# TPMS.net
KiCad netlist of a schematic drawn in EAGLE
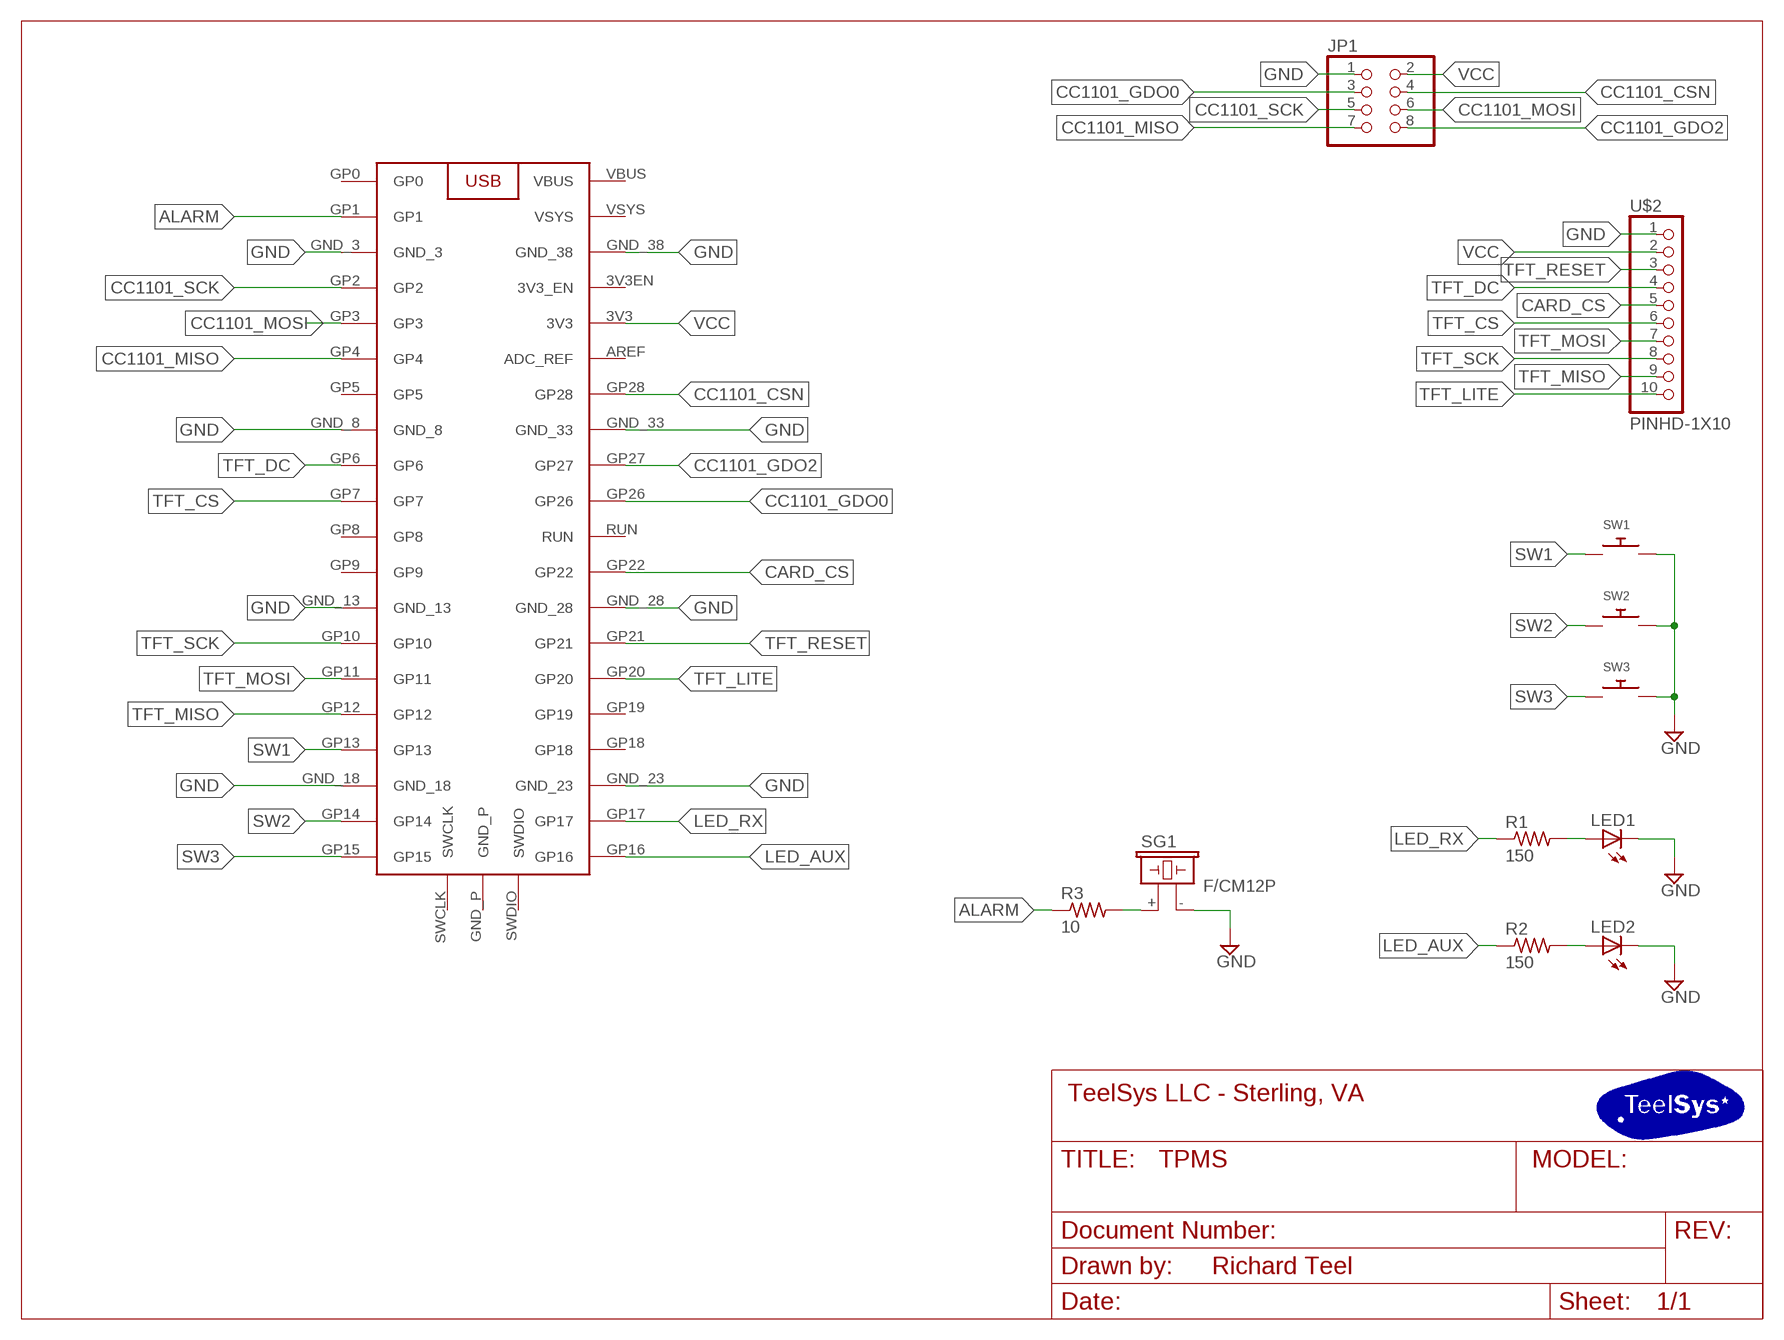
[diagram p0: schematic, sheet 1]

(export (version "E")
  (design (tool "Eeschema 10.0.6"))
  (components
    (comp (ref "JP1")
      (value "PINHD-2X4")
      (footprint "eagle-import:2X04")
      (libsource (lib "eagle-import") (part "PINHD-2X4"))
    )
    (comp (ref "LED1")
      (value "LED3MM")
      (footprint "eagle-import:LED3MM")
      (libsource (lib "eagle-import") (part "LED3MM"))
    )
    (comp (ref "LED2")
      (value "LED3MM")
      (footprint "eagle-import:LED3MM")
      (libsource (lib "eagle-import") (part "LED3MM"))
    )
    (comp (ref "R1")
      (value "150")
      (footprint "eagle-import:M0805")
      (libsource (lib "eagle-import") (part "R-US_M0805"))
    )
    (comp (ref "R2")
      (value "150")
      (footprint "eagle-import:M0805")
      (libsource (lib "eagle-import") (part "R-US_M0805"))
    )
    (comp (ref "R3")
      (value "10")
      (footprint "eagle-import:M0805")
      (libsource (lib "eagle-import") (part "R-US_M0805"))
    )
    (comp (ref "SG1")
      (value "F/CM12P")
      (footprint "eagle-import:F_CM12P")
      (libsource (lib "eagle-import") (part "F/CM12P"))
    )
    (comp (ref "SW1")
      (value "SWITCH_PUSHBUTTONEVQ-PE")
      (footprint "eagle-import:TACT_PANA-EVQ")
      (libsource (lib "eagle-import") (part "SWITCH_PUSHBUTTONEVQ-PE"))
    )
    (comp (ref "SW2")
      (value "SWITCH_PUSHBUTTONEVQ-PE")
      (footprint "eagle-import:TACT_PANA-EVQ")
      (libsource (lib "eagle-import") (part "SWITCH_PUSHBUTTONEVQ-PE"))
    )
    (comp (ref "SW3")
      (value "SWITCH_PUSHBUTTONEVQ-PE")
      (footprint "eagle-import:TACT_PANA-EVQ")
      (libsource (lib "eagle-import") (part "SWITCH_PUSHBUTTONEVQ-PE"))
    )
    (comp (ref "U$1")
      (value "RASPBERRY_PI_PICORASPBERRY_PI_PICO")
      (footprint "eagle-import:RASPBERRY_PI_PICO")
      (libsource (lib "eagle-import") (part "RASPBERRY_PI_PICORASPBERRY_PI_PICO"))
    )
    (comp (ref "U$2")
      (value "PINHD-1X10")
      (footprint "eagle-import:1X10-BIG")
      (libsource (lib "eagle-import") (part "PINHD-1X10"))
    )
  )
  (nets
    (net (code "1") (name "ALARM") (class "Default")
      (node (ref "R3") (pin "1") (pinfunction "1_1") (pintype "passive"))
      (node (ref "U$1") (pin "GP1") (pinfunction "GP1_GP1") (pintype "bidirectional"))
    )
    (net (code "2") (name "CARD_CS") (class "Default")
      (node (ref "U$1") (pin "GP22") (pinfunction "GP22_GP22") (pintype "bidirectional"))
      (node (ref "U$2") (pin "5") (pinfunction "5_5") (pintype "passive"))
    )
    (net (code "3") (name "CC1101_CSN") (class "Default")
      (node (ref "JP1") (pin "4") (pinfunction "4_4") (pintype "passive"))
      (node (ref "U$1") (pin "GP28") (pinfunction "GP28_GP28") (pintype "bidirectional"))
    )
    (net (code "4") (name "CC1101_GDO0") (class "Default")
      (node (ref "JP1") (pin "3") (pinfunction "3_3") (pintype "passive"))
      (node (ref "U$1") (pin "GP26") (pinfunction "GP26_GP26") (pintype "bidirectional"))
    )
    (net (code "5") (name "CC1101_GDO2") (class "Default")
      (node (ref "JP1") (pin "8") (pinfunction "8_8") (pintype "passive"))
      (node (ref "U$1") (pin "GP27") (pinfunction "GP27_GP27") (pintype "bidirectional"))
    )
    (net (code "6") (name "CC1101_MISO") (class "Default")
      (node (ref "JP1") (pin "7") (pinfunction "7_7") (pintype "passive"))
      (node (ref "U$1") (pin "GP4") (pinfunction "GP4_GP4") (pintype "bidirectional"))
    )
    (net (code "7") (name "CC1101_MOSI") (class "Default")
      (node (ref "JP1") (pin "6") (pinfunction "6_6") (pintype "passive"))
      (node (ref "U$1") (pin "GP3") (pinfunction "GP3_GP3") (pintype "bidirectional"))
    )
    (net (code "8") (name "CC1101_SCK") (class "Default")
      (node (ref "JP1") (pin "5") (pinfunction "5_5") (pintype "passive"))
      (node (ref "U$1") (pin "GP2") (pinfunction "GP2_GP2") (pintype "bidirectional"))
    )
    (net (code "9") (name "GND") (class "Default")
      (node (ref "JP1") (pin "1") (pinfunction "1_1") (pintype "passive"))
      (node (ref "LED1") (pin "K") (pinfunction "C_K") (pintype "passive"))
      (node (ref "LED2") (pin "K") (pinfunction "C_K") (pintype "passive"))
      (node (ref "SG1") (pin "-") (pinfunction "2_-") (pintype "passive"))
      (node (ref "SW1") (pin "P$2") (pinfunction "P$2_P$2") (pintype "passive"))
      (node (ref "SW2") (pin "P$2") (pinfunction "P$2_P$2") (pintype "passive"))
      (node (ref "SW3") (pin "P$2") (pinfunction "P$2_P$2") (pintype "passive"))
      (node (ref "U$1") (pin "GND_13") (pinfunction "GND_13_GND_13") (pintype "bidirectional"))
      (node (ref "U$1") (pin "GND_18") (pinfunction "GND_18_GND_18") (pintype "bidirectional"))
      (node (ref "U$1") (pin "GND_23") (pinfunction "GND_23_GND_23") (pintype "bidirectional"))
      (node (ref "U$1") (pin "GND_28") (pinfunction "GND_28_GND_28") (pintype "bidirectional"))
      (node (ref "U$1") (pin "GND_3") (pinfunction "GND_3_GND_3") (pintype "bidirectional"))
      (node (ref "U$1") (pin "GND_33") (pinfunction "GND_33_GND_33") (pintype "bidirectional"))
      (node (ref "U$1") (pin "GND_38") (pinfunction "GND_38_GND_38") (pintype "bidirectional"))
      (node (ref "U$1") (pin "GND_8") (pinfunction "GND_8_GND_8") (pintype "bidirectional"))
      (node (ref "U$2") (pin "1") (pinfunction "1_1") (pintype "passive"))
    )
    (net (code "10") (name "LED_AUX") (class "Default")
      (node (ref "R2") (pin "1") (pinfunction "1_1") (pintype "passive"))
      (node (ref "U$1") (pin "GP16") (pinfunction "GP16_GP16") (pintype "bidirectional"))
    )
    (net (code "11") (name "LED_RX") (class "Default")
      (node (ref "R1") (pin "1") (pinfunction "1_1") (pintype "passive"))
      (node (ref "U$1") (pin "GP17") (pinfunction "GP17_GP17") (pintype "bidirectional"))
    )
    (net (code "12") (name "Net-(LED1-PadA)") (class "Default")
      (node (ref "LED1") (pin "A") (pinfunction "A_A") (pintype "passive"))
      (node (ref "R1") (pin "2") (pinfunction "2_2") (pintype "passive"))
    )
    (net (code "13") (name "Net-(LED2-PadA)") (class "Default")
      (node (ref "LED2") (pin "A") (pinfunction "A_A") (pintype "passive"))
      (node (ref "R2") (pin "2") (pinfunction "2_2") (pintype "passive"))
    )
    (net (code "14") (name "Net-(SG1-1)") (class "Default")
      (node (ref "R3") (pin "2") (pinfunction "2_2") (pintype "passive"))
      (node (ref "SG1") (pin "+") (pinfunction "1_+") (pintype "passive"))
    )
    (net (code "15") (name "SW1") (class "Default")
      (node (ref "SW1") (pin "P$1") (pinfunction "P$1_P$1") (pintype "passive"))
      (node (ref "U$1") (pin "GP13") (pinfunction "GP13_GP13") (pintype "bidirectional"))
    )
    (net (code "16") (name "SW2") (class "Default")
      (node (ref "SW2") (pin "P$1") (pinfunction "P$1_P$1") (pintype "passive"))
      (node (ref "U$1") (pin "GP14") (pinfunction "GP14_GP14") (pintype "bidirectional"))
    )
    (net (code "17") (name "SW3") (class "Default")
      (node (ref "SW3") (pin "P$1") (pinfunction "P$1_P$1") (pintype "passive"))
      (node (ref "U$1") (pin "GP15") (pinfunction "GP15_GP15") (pintype "bidirectional"))
    )
    (net (code "18") (name "TFT_CS") (class "Default")
      (node (ref "U$1") (pin "GP7") (pinfunction "GP7_GP7") (pintype "bidirectional"))
      (node (ref "U$2") (pin "6") (pinfunction "6_6") (pintype "passive"))
    )
    (net (code "19") (name "TFT_DC") (class "Default")
      (node (ref "U$1") (pin "GP6") (pinfunction "GP6_GP6") (pintype "bidirectional"))
      (node (ref "U$2") (pin "4") (pinfunction "4_4") (pintype "passive"))
    )
    (net (code "20") (name "TFT_LITE") (class "Default")
      (node (ref "U$1") (pin "GP20") (pinfunction "GP20_GP20") (pintype "bidirectional"))
      (node (ref "U$2") (pin "10") (pinfunction "10_10") (pintype "passive"))
    )
    (net (code "21") (name "TFT_MISO") (class "Default")
      (node (ref "U$1") (pin "GP12") (pinfunction "GP12_GP12") (pintype "bidirectional"))
      (node (ref "U$2") (pin "9") (pinfunction "9_9") (pintype "passive"))
    )
    (net (code "22") (name "TFT_MOSI") (class "Default")
      (node (ref "U$1") (pin "GP11") (pinfunction "GP11_GP11") (pintype "bidirectional"))
      (node (ref "U$2") (pin "7") (pinfunction "7_7") (pintype "passive"))
    )
    (net (code "23") (name "TFT_RESET") (class "Default")
      (node (ref "U$1") (pin "GP21") (pinfunction "GP21_GP21") (pintype "bidirectional"))
      (node (ref "U$2") (pin "3") (pinfunction "3_3") (pintype "passive"))
    )
    (net (code "24") (name "TFT_SCK") (class "Default")
      (node (ref "U$1") (pin "GP10") (pinfunction "GP10_GP10") (pintype "bidirectional"))
      (node (ref "U$2") (pin "8") (pinfunction "8_8") (pintype "passive"))
    )
    (net (code "25") (name "VCC") (class "Default")
      (node (ref "JP1") (pin "2") (pinfunction "2_2") (pintype "passive"))
      (node (ref "U$1") (pin "3V3") (pinfunction "3V3_3V3") (pintype "bidirectional"))
      (node (ref "U$2") (pin "2") (pinfunction "2_2") (pintype "passive"))
    )
    (net (code "26") (name "unconnected-(U$1-3V3_EN-Pad3V3EN)") (class "Default")
      (node (ref "U$1") (pin "3V3EN") (pinfunction "3V3_EN_3V3EN") (pintype "bidirectional"))
    )
    (net (code "27") (name "unconnected-(U$1-ADC_REF-PadAREF)") (class "Default")
      (node (ref "U$1") (pin "AREF") (pinfunction "ADC_REF_AREF") (pintype "bidirectional"))
    )
    (net (code "28") (name "unconnected-(U$1-PadGND_P)") (class "Default")
      (node (ref "U$1") (pin "GND_P") (pinfunction "GND_P_GND_P") (pintype "bidirectional"))
    )
    (net (code "29") (name "unconnected-(U$1-PadGP0)") (class "Default")
      (node (ref "U$1") (pin "GP0") (pinfunction "GP0_GP0") (pintype "bidirectional"))
    )
    (net (code "30") (name "unconnected-(U$1-PadGP5)") (class "Default")
      (node (ref "U$1") (pin "GP5") (pinfunction "GP5_GP5") (pintype "bidirectional"))
    )
    (net (code "31") (name "unconnected-(U$1-PadGP8)") (class "Default")
      (node (ref "U$1") (pin "GP8") (pinfunction "GP8_GP8") (pintype "bidirectional"))
    )
    (net (code "32") (name "unconnected-(U$1-PadGP9)") (class "Default")
      (node (ref "U$1") (pin "GP9") (pinfunction "GP9_GP9") (pintype "bidirectional"))
    )
    (net (code "33") (name "unconnected-(U$1-PadGP18)") (class "Default")
      (node (ref "U$1") (pin "GP18") (pinfunction "GP18_GP18") (pintype "bidirectional"))
    )
    (net (code "34") (name "unconnected-(U$1-PadGP19)") (class "Default")
      (node (ref "U$1") (pin "GP19") (pinfunction "GP19_GP19") (pintype "bidirectional"))
    )
    (net (code "35") (name "unconnected-(U$1-PadRUN)") (class "Default")
      (node (ref "U$1") (pin "RUN") (pinfunction "RUN_RUN") (pintype "bidirectional"))
    )
    (net (code "36") (name "unconnected-(U$1-PadSWCLK)") (class "Default")
      (node (ref "U$1") (pin "SWCLK") (pinfunction "SWCLK_SWCLK") (pintype "bidirectional"))
    )
    (net (code "37") (name "unconnected-(U$1-PadSWDIO)") (class "Default")
      (node (ref "U$1") (pin "SWDIO") (pinfunction "SWDIO_SWDIO") (pintype "bidirectional"))
    )
    (net (code "38") (name "unconnected-(U$1-PadVBUS)") (class "Default")
      (node (ref "U$1") (pin "VBUS") (pinfunction "VBUS_VBUS") (pintype "bidirectional"))
    )
    (net (code "39") (name "unconnected-(U$1-PadVSYS)") (class "Default")
      (node (ref "U$1") (pin "VSYS") (pinfunction "VSYS_VSYS") (pintype "bidirectional"))
    )
  )
)
